# QUARTZ_01.net
KiCad netlist of a schematic drawn in EasyEDA Pro
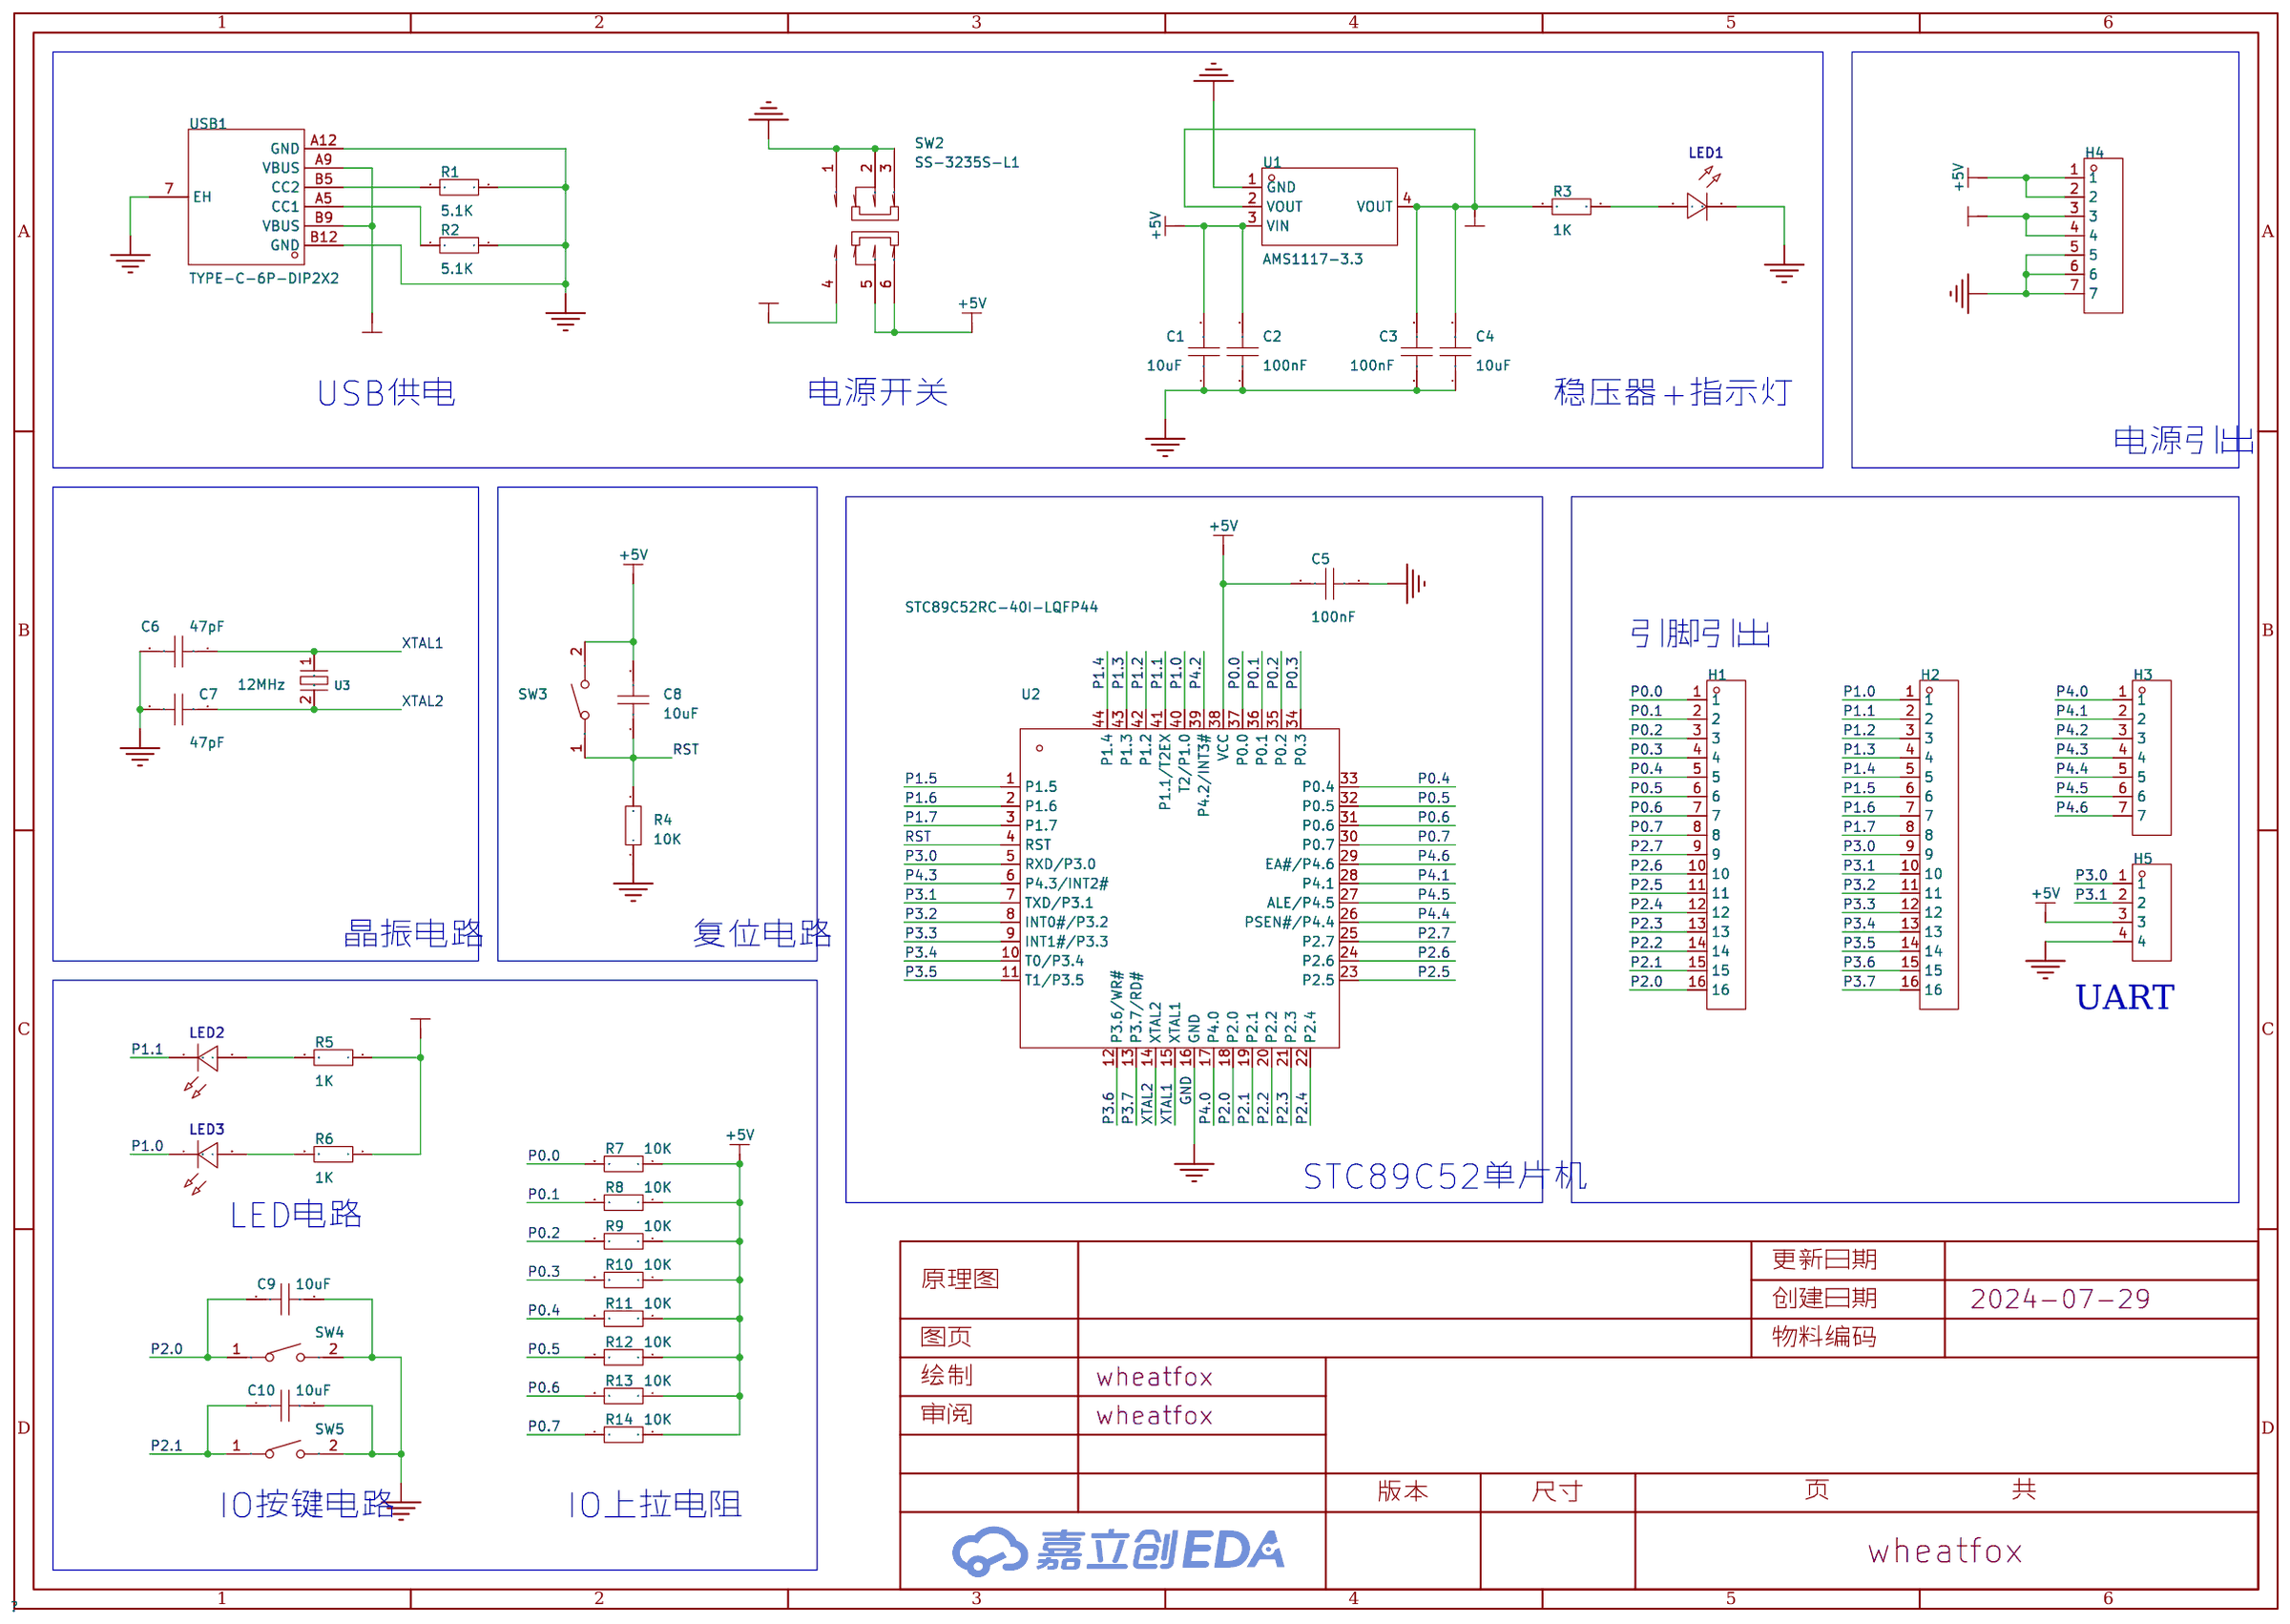
[diagram p0: schematic sheet]

(export (version "E")
  (design (tool "Eeschema 10.0.6"))
  (components
    (comp (ref "C1")
      (value "10uF")
      (footprint "easyedapro:C0805")
      (libsource (lib "easyedapro") (part "CapAcitance"))
    )
    (comp (ref "C2")
      (value "100nF")
      (footprint "easyedapro:C0805")
      (libsource (lib "easyedapro") (part "CapAcitance"))
    )
    (comp (ref "C3")
      (value "100nF")
      (footprint "easyedapro:C0805")
      (libsource (lib "easyedapro") (part "CapAcitance"))
    )
    (comp (ref "C4")
      (value "10uF")
      (footprint "easyedapro:C0805")
      (libsource (lib "easyedapro") (part "CapAcitance"))
    )
    (comp (ref "C5")
      (value "100nF")
      (footprint "easyedapro:C0805")
      (libsource (lib "easyedapro") (part "CapAcitance"))
    )
    (comp (ref "C6")
      (value "47pF")
      (footprint "easyedapro:C0805")
      (libsource (lib "easyedapro") (part "CapAcitance"))
    )
    (comp (ref "C7")
      (value "47pF")
      (footprint "easyedapro:C0805")
      (libsource (lib "easyedapro") (part "CapAcitance"))
    )
    (comp (ref "C8")
      (value "10uF")
      (footprint "easyedapro:C0805")
      (libsource (lib "easyedapro") (part "CapAcitance"))
    )
    (comp (ref "C9")
      (value "10uF")
      (footprint "easyedapro:C0805")
      (libsource (lib "easyedapro") (part "CapAcitance"))
    )
    (comp (ref "C10")
      (value "10uF")
      (footprint "easyedapro:C0805")
      (libsource (lib "easyedapro") (part "CapAcitance"))
    )
    (comp (ref "H1")
      (value "~")
      (footprint "easyedapro:HDR-TH_16P-P2.54-V-M")
      (libsource (lib "easyedapro") (part "HDR_2.54-1x16P"))
    )
    (comp (ref "H2")
      (value "~")
      (footprint "easyedapro:HDR-TH_16P-P2.54-V-M")
      (libsource (lib "easyedapro") (part "HDR_2.54-1x16P"))
    )
    (comp (ref "H3")
      (value "~")
      (footprint "easyedapro:HDR-TH_7P-P2.54-V-M")
      (fields (field (name "Manufacturer Part") "PZ254V-11-07P") (field (name "Manufacturer") "XFCN(兴飞)"))
      (libsource (lib "easyedapro") (part "PZ254V-11-07P"))
    )
    (comp (ref "H4")
      (value "~")
      (footprint "easyedapro:HDR-TH_7P-P2.54-V-M")
      (fields (field (name "Manufacturer Part") "PZ254V-11-07P") (field (name "Manufacturer") "XFCN(兴飞)"))
      (libsource (lib "easyedapro") (part "PZ254V-11-07P"))
    )
    (comp (ref "H5")
      (value "~")
      (footprint "easyedapro:HDR-TH_4P-P2.54-V-M")
      (libsource (lib "easyedapro") (part "PZ254V-11-04P"))
    )
    (comp (ref "LED1")
      (value "~")
      (footprint "easyedapro:LED_0805")
      (libsource (lib "easyedapro") (part "LED_G"))
    )
    (comp (ref "LED2")
      (value "~")
      (footprint "easyedapro:LED_0805")
      (libsource (lib "easyedapro") (part "LED_G"))
    )
    (comp (ref "LED3")
      (value "~")
      (footprint "easyedapro:LED_0805")
      (libsource (lib "easyedapro") (part "LED_G"))
    )
    (comp (ref "R1") (value "5.1K") (footprint "easyedapro:R0805") (libsource (lib "easyedapro") (part "电阻")))
    (comp (ref "R2") (value "5.1K") (footprint "easyedapro:R0805") (libsource (lib "easyedapro") (part "电阻")))
    (comp (ref "R3") (value "1K") (footprint "easyedapro:R0805") (libsource (lib "easyedapro") (part "电阻")))
    (comp (ref "R4") (value "10K") (footprint "easyedapro:R0805") (libsource (lib "easyedapro") (part "电阻")))
    (comp (ref "R5") (value "1K") (footprint "easyedapro:R0805") (libsource (lib "easyedapro") (part "电阻")))
    (comp (ref "R6") (value "1K") (footprint "easyedapro:R0805") (libsource (lib "easyedapro") (part "电阻")))
    (comp (ref "R7") (value "10K") (footprint "easyedapro:R0805") (libsource (lib "easyedapro") (part "电阻")))
    (comp (ref "R8") (value "10K") (footprint "easyedapro:R0805") (libsource (lib "easyedapro") (part "电阻")))
    (comp (ref "R9") (value "10K") (footprint "easyedapro:R0805") (libsource (lib "easyedapro") (part "电阻")))
    (comp (ref "R10") (value "10K") (footprint "easyedapro:R0805") (libsource (lib "easyedapro") (part "电阻")))
    (comp (ref "R11") (value "10K") (footprint "easyedapro:R0805") (libsource (lib "easyedapro") (part "电阻")))
    (comp (ref "R12") (value "10K") (footprint "easyedapro:R0805") (libsource (lib "easyedapro") (part "电阻")))
    (comp (ref "R13") (value "10K") (footprint "easyedapro:R0805") (libsource (lib "easyedapro") (part "电阻")))
    (comp (ref "R14") (value "10K") (footprint "easyedapro:R0805") (libsource (lib "easyedapro") (part "电阻")))
    (comp (ref "SW2")
      (value "SS-3235S-L1")
      (footprint "easyedapro:SW-SMD_SS-3235S-LX")
      (description "电路结构:双刀双掷;安装方式:卧贴;开关颜色:黑色;额定电流(DC):50mA;额定电压(DC):12V;额定电流(AC):50mA;额定电压(AC):12V;机械寿命:1万次;")
      (fields (field (name "Manufacturer") "XKB Connectivity(中国星坤)"))
      (libsource (lib "easyedapro") (part "SS-3235S-L1"))
    )
    (comp (ref "SW3")
      (value "轻触按键3*4*H")
      (footprint "easyedapro:SW-SMD_L4.0-W2.9-LS5.0")
      (libsource (lib "easyedapro") (part "轻触按键3*4*H"))
    )
    (comp (ref "SW4")
      (value "轻触按键3*4*H")
      (footprint "easyedapro:SW-SMD_L4.0-W2.9-LS5.0")
      (libsource (lib "easyedapro") (part "轻触按键3*4*H"))
    )
    (comp (ref "SW5")
      (value "轻触按键3*4*H")
      (footprint "easyedapro:SW-SMD_L4.0-W2.9-LS5.0")
      (libsource (lib "easyedapro") (part "轻触按键3*4*H"))
    )
    (comp (ref "U1")
      (value "AMS1117-3.3")
      (footprint "easyedapro:SOT-223-3_L6.5-W3.4-P2.30-LS7.0-BR")
      (description "输出类型:固定;最大输入电压:-;输出电压:3.3V;最大输出电流:1A;电源纹波抑制比(PSRR):72dB@(120Hz);输出极性:正极;")
      (fields (field (name "Manufacturer") "AMS"))
      (libsource (lib "easyedapro") (part "AMS1117-3.3"))
    )
    (comp (ref "U2")
      (value "STC89C52RC-40I-LQFP44")
      (footprint "easyedapro:LQFP-44_L10.0-W10.0-P0.80-LS12.0-BL")
      (description "CPU内核:51系列;程序存储容量:8KB;RAM总容量:512Byte;GPIO端口数量:39;工作电压范围:3.3V~5.5V;CPU最大主频:-;程序存储器类型:FLASH;")
      (fields (field (name "Manufacturer") "STC(宏晶)"))
      (libsource (lib "easyedapro") (part "STC89C52RC-40I_C8707"))
    )
    (comp (ref "U3")
      (value "12MHz")
      (footprint "easyedapro:CRYSTAL-SMD_L11.4-W4.7-LS12.7")
      (description "频率:12MHz;常温频差:±30ppm;外接负载电容:18pF;频率稳定度(全温):±35ppm;")
      (fields
        (field (name "Manufacturer Part") "ABLS-12.000MHZ-B4H-T")
        (field (name "Manufacturer") "ABRACON")
      )
      (libsource (lib "easyedapro") (part "ABLS-12.000MHZ-B4H-T"))
    )
    (comp (ref "USB1")
      (value "TYPE-C-6P-DIP2X2")
      (footprint "easyedapro:TYPE-C-SMD_TYPE-C-6P")
      (libsource (lib "easyedapro") (part "TYPE-C-6P-DIP2X2"))
    )
  )
  (nets
    (net (code "1") (name "+5V") (class "Default")
      (node (ref "C1") (pin "2") (pinfunction "2_2") (pintype "input"))
      (node (ref "C2") (pin "2") (pinfunction "2_2") (pintype "input"))
      (node (ref "C5") (pin "2") (pinfunction "2_2") (pintype "input"))
      (node (ref "C8") (pin "1") (pinfunction "1_1") (pintype "input"))
      (node (ref "H4") (pin "1") (pinfunction "1_1") (pintype "unspecified"))
      (node (ref "H4") (pin "2") (pinfunction "2_2") (pintype "unspecified"))
      (node (ref "H5") (pin "3") (pinfunction "3_3") (pintype "unspecified"))
      (node (ref "R10") (pin "1") (pinfunction "1_1") (pintype "input"))
      (node (ref "R11") (pin "1") (pinfunction "1_1") (pintype "input"))
      (node (ref "R12") (pin "1") (pinfunction "1_1") (pintype "input"))
      (node (ref "R13") (pin "1") (pinfunction "1_1") (pintype "input"))
      (node (ref "R14") (pin "1") (pinfunction "1_1") (pintype "input"))
      (node (ref "R7") (pin "1") (pinfunction "1_1") (pintype "input"))
      (node (ref "R8") (pin "1") (pinfunction "1_1") (pintype "input"))
      (node (ref "R9") (pin "1") (pinfunction "1_1") (pintype "input"))
      (node (ref "SW2") (pin "5") (pinfunction "5_5") (pintype "unspecified"))
      (node (ref "SW2") (pin "6") (pinfunction "6_6") (pintype "unspecified"))
      (node (ref "SW3") (pin "2") (pinfunction "2_2") (pintype "unspecified"))
      (node (ref "U1") (pin "3") (pinfunction "VIN_3") (pintype "unspecified"))
      (node (ref "U2") (pin "38") (pinfunction "VCC_38") (pintype "unspecified"))
    )
    (net (code "2") (name "/P0.0") (class "Default")
      (node (ref "H1") (pin "1") (pinfunction "1_1") (pintype "input"))
      (node (ref "R7") (pin "2") (pinfunction "2_2") (pintype "input"))
      (node (ref "U2") (pin "37") (pinfunction "P0.0_37") (pintype "unspecified"))
    )
    (net (code "3") (name "/P0.1") (class "Default")
      (node (ref "H1") (pin "2") (pinfunction "2_2") (pintype "input"))
      (node (ref "R8") (pin "2") (pinfunction "2_2") (pintype "input"))
      (node (ref "U2") (pin "36") (pinfunction "P0.1_36") (pintype "unspecified"))
    )
    (net (code "4") (name "/P0.2") (class "Default")
      (node (ref "H1") (pin "3") (pinfunction "3_3") (pintype "input"))
      (node (ref "R9") (pin "2") (pinfunction "2_2") (pintype "input"))
      (node (ref "U2") (pin "35") (pinfunction "P0.2_35") (pintype "unspecified"))
    )
    (net (code "5") (name "/P0.3") (class "Default")
      (node (ref "H1") (pin "4") (pinfunction "4_4") (pintype "input"))
      (node (ref "R10") (pin "2") (pinfunction "2_2") (pintype "input"))
      (node (ref "U2") (pin "34") (pinfunction "P0.3_34") (pintype "unspecified"))
    )
    (net (code "6") (name "/P0.4") (class "Default")
      (node (ref "H1") (pin "5") (pinfunction "5_5") (pintype "input"))
      (node (ref "R11") (pin "2") (pinfunction "2_2") (pintype "input"))
      (node (ref "U2") (pin "33") (pinfunction "P0.4_33") (pintype "unspecified"))
    )
    (net (code "7") (name "/P0.5") (class "Default")
      (node (ref "H1") (pin "6") (pinfunction "6_6") (pintype "input"))
      (node (ref "R12") (pin "2") (pinfunction "2_2") (pintype "input"))
      (node (ref "U2") (pin "32") (pinfunction "P0.5_32") (pintype "unspecified"))
    )
    (net (code "8") (name "/P0.6") (class "Default")
      (node (ref "H1") (pin "7") (pinfunction "7_7") (pintype "input"))
      (node (ref "R13") (pin "2") (pinfunction "2_2") (pintype "input"))
      (node (ref "U2") (pin "31") (pinfunction "P0.6_31") (pintype "unspecified"))
    )
    (net (code "9") (name "/P0.7") (class "Default")
      (node (ref "H1") (pin "8") (pinfunction "8_8") (pintype "input"))
      (node (ref "R14") (pin "2") (pinfunction "2_2") (pintype "input"))
      (node (ref "U2") (pin "30") (pinfunction "P0.7_30") (pintype "unspecified"))
    )
    (net (code "10") (name "/P1.0") (class "Default")
      (node (ref "H2") (pin "1") (pinfunction "1_1") (pintype "input"))
      (node (ref "LED3") (pin "1") (pinfunction "C_1") (pintype "input"))
      (node (ref "U2") (pin "40") (pinfunction "T2/P1.0_40") (pintype "unspecified"))
    )
    (net (code "11") (name "/P1.1") (class "Default")
      (node (ref "H2") (pin "2") (pinfunction "2_2") (pintype "input"))
      (node (ref "LED2") (pin "1") (pinfunction "C_1") (pintype "input"))
      (node (ref "U2") (pin "41") (pinfunction "P1.1/T2EX_41") (pintype "unspecified"))
    )
    (net (code "12") (name "/P1.2") (class "Default")
      (node (ref "H2") (pin "3") (pinfunction "3_3") (pintype "input"))
      (node (ref "U2") (pin "42") (pinfunction "P1.2_42") (pintype "unspecified"))
    )
    (net (code "13") (name "/P1.3") (class "Default")
      (node (ref "H2") (pin "4") (pinfunction "4_4") (pintype "input"))
      (node (ref "U2") (pin "43") (pinfunction "P1.3_43") (pintype "unspecified"))
    )
    (net (code "14") (name "/P1.4") (class "Default")
      (node (ref "H2") (pin "5") (pinfunction "5_5") (pintype "input"))
      (node (ref "U2") (pin "44") (pinfunction "P1.4_44") (pintype "unspecified"))
    )
    (net (code "15") (name "/P1.5") (class "Default")
      (node (ref "H2") (pin "6") (pinfunction "6_6") (pintype "input"))
      (node (ref "U2") (pin "1") (pinfunction "P1.5_1") (pintype "unspecified"))
    )
    (net (code "16") (name "/P1.6") (class "Default")
      (node (ref "H2") (pin "7") (pinfunction "7_7") (pintype "input"))
      (node (ref "U2") (pin "2") (pinfunction "P1.6_2") (pintype "unspecified"))
    )
    (net (code "17") (name "/P1.7") (class "Default")
      (node (ref "H2") (pin "8") (pinfunction "8_8") (pintype "input"))
      (node (ref "U2") (pin "3") (pinfunction "P1.7_3") (pintype "unspecified"))
    )
    (net (code "18") (name "/P2.0") (class "Default")
      (node (ref "C9") (pin "1") (pinfunction "1_1") (pintype "input"))
      (node (ref "H1") (pin "16") (pinfunction "16_16") (pintype "input"))
      (node (ref "SW4") (pin "1") (pinfunction "1_1") (pintype "unspecified"))
      (node (ref "U2") (pin "18") (pinfunction "P2.0_18") (pintype "unspecified"))
    )
    (net (code "19") (name "/P2.1") (class "Default")
      (node (ref "C10") (pin "1") (pinfunction "1_1") (pintype "input"))
      (node (ref "H1") (pin "15") (pinfunction "15_15") (pintype "input"))
      (node (ref "SW5") (pin "1") (pinfunction "1_1") (pintype "unspecified"))
      (node (ref "U2") (pin "19") (pinfunction "P2.1_19") (pintype "unspecified"))
    )
    (net (code "20") (name "/P2.2") (class "Default")
      (node (ref "H1") (pin "14") (pinfunction "14_14") (pintype "input"))
      (node (ref "U2") (pin "20") (pinfunction "P2.2_20") (pintype "unspecified"))
    )
    (net (code "21") (name "/P2.3") (class "Default")
      (node (ref "H1") (pin "13") (pinfunction "13_13") (pintype "input"))
      (node (ref "U2") (pin "21") (pinfunction "P2.3_21") (pintype "unspecified"))
    )
    (net (code "22") (name "/P2.4") (class "Default")
      (node (ref "H1") (pin "12") (pinfunction "12_12") (pintype "input"))
      (node (ref "U2") (pin "22") (pinfunction "P2.4_22") (pintype "unspecified"))
    )
    (net (code "23") (name "/P2.5") (class "Default")
      (node (ref "H1") (pin "11") (pinfunction "11_11") (pintype "input"))
      (node (ref "U2") (pin "23") (pinfunction "P2.5_23") (pintype "unspecified"))
    )
    (net (code "24") (name "/P2.6") (class "Default")
      (node (ref "H1") (pin "10") (pinfunction "10_10") (pintype "input"))
      (node (ref "U2") (pin "24") (pinfunction "P2.6_24") (pintype "unspecified"))
    )
    (net (code "25") (name "/P2.7") (class "Default")
      (node (ref "H1") (pin "9") (pinfunction "9_9") (pintype "input"))
      (node (ref "U2") (pin "25") (pinfunction "P2.7_25") (pintype "unspecified"))
    )
    (net (code "26") (name "/P3.0") (class "Default")
      (node (ref "H2") (pin "9") (pinfunction "9_9") (pintype "input"))
      (node (ref "H5") (pin "1") (pinfunction "1_1") (pintype "unspecified"))
      (node (ref "U2") (pin "5") (pinfunction "RXD/P3.0_5") (pintype "unspecified"))
    )
    (net (code "27") (name "/P3.1") (class "Default")
      (node (ref "H2") (pin "10") (pinfunction "10_10") (pintype "input"))
      (node (ref "H5") (pin "2") (pinfunction "2_2") (pintype "unspecified"))
      (node (ref "U2") (pin "7") (pinfunction "TXD/P3.1_7") (pintype "unspecified"))
    )
    (net (code "28") (name "/P3.2") (class "Default")
      (node (ref "H2") (pin "11") (pinfunction "11_11") (pintype "input"))
      (node (ref "U2") (pin "8") (pinfunction "INT0#/P3.2_8") (pintype "unspecified"))
    )
    (net (code "29") (name "/P3.3") (class "Default")
      (node (ref "H2") (pin "12") (pinfunction "12_12") (pintype "input"))
      (node (ref "U2") (pin "9") (pinfunction "INT1#/P3.3_9") (pintype "unspecified"))
    )
    (net (code "30") (name "/P3.4") (class "Default")
      (node (ref "H2") (pin "13") (pinfunction "13_13") (pintype "input"))
      (node (ref "U2") (pin "10") (pinfunction "T0/P3.4_10") (pintype "unspecified"))
    )
    (net (code "31") (name "/P3.5") (class "Default")
      (node (ref "H2") (pin "14") (pinfunction "14_14") (pintype "input"))
      (node (ref "U2") (pin "11") (pinfunction "T1/P3.5_11") (pintype "unspecified"))
    )
    (net (code "32") (name "/P3.6") (class "Default")
      (node (ref "H2") (pin "15") (pinfunction "15_15") (pintype "input"))
      (node (ref "U2") (pin "12") (pinfunction "P3.6/WR#_12") (pintype "unspecified"))
    )
    (net (code "33") (name "/P3.7") (class "Default")
      (node (ref "H2") (pin "16") (pinfunction "16_16") (pintype "input"))
      (node (ref "U2") (pin "13") (pinfunction "P3.7/RD#_13") (pintype "unspecified"))
    )
    (net (code "34") (name "/P4.0") (class "Default")
      (node (ref "H3") (pin "1") (pinfunction "1_1") (pintype "unspecified"))
      (node (ref "U2") (pin "17") (pinfunction "P4.0_17") (pintype "unspecified"))
    )
    (net (code "35") (name "/P4.1") (class "Default")
      (node (ref "H3") (pin "2") (pinfunction "2_2") (pintype "unspecified"))
      (node (ref "U2") (pin "28") (pinfunction "P4.1_28") (pintype "unspecified"))
    )
    (net (code "36") (name "/P4.2") (class "Default")
      (node (ref "H3") (pin "3") (pinfunction "3_3") (pintype "unspecified"))
      (node (ref "U2") (pin "39") (pinfunction "P4.2/INT3#_39") (pintype "unspecified"))
    )
    (net (code "37") (name "/P4.3") (class "Default")
      (node (ref "H3") (pin "4") (pinfunction "4_4") (pintype "unspecified"))
      (node (ref "U2") (pin "6") (pinfunction "P4.3/INT2#_6") (pintype "unspecified"))
    )
    (net (code "38") (name "/P4.4") (class "Default")
      (node (ref "H3") (pin "5") (pinfunction "5_5") (pintype "unspecified"))
      (node (ref "U2") (pin "26") (pinfunction "PSEN#/P4.4_26") (pintype "unspecified"))
    )
    (net (code "39") (name "/P4.5") (class "Default")
      (node (ref "H3") (pin "6") (pinfunction "6_6") (pintype "unspecified"))
      (node (ref "U2") (pin "27") (pinfunction "ALE/P4.5_27") (pintype "unspecified"))
    )
    (net (code "40") (name "/P4.6") (class "Default")
      (node (ref "H3") (pin "7") (pinfunction "7_7") (pintype "unspecified"))
      (node (ref "U2") (pin "29") (pinfunction "EA#/P4.6_29") (pintype "unspecified"))
    )
    (net (code "41") (name "/RST") (class "Default")
      (node (ref "C8") (pin "2") (pinfunction "2_2") (pintype "input"))
      (node (ref "R4") (pin "2") (pinfunction "2_2") (pintype "input"))
      (node (ref "SW3") (pin "1") (pinfunction "1_1") (pintype "unspecified"))
      (node (ref "U2") (pin "4") (pinfunction "RST_4") (pintype "unspecified"))
    )
    (net (code "42") (name "/XTAL1") (class "Default")
      (node (ref "C6") (pin "1") (pinfunction "1_1") (pintype "input"))
      (node (ref "U2") (pin "15") (pinfunction "XTAL1_15") (pintype "unspecified"))
      (node (ref "U3") (pin "1") (pinfunction "1_1") (pintype "input"))
    )
    (net (code "43") (name "/XTAL2") (class "Default")
      (node (ref "C7") (pin "1") (pinfunction "1_1") (pintype "input"))
      (node (ref "U2") (pin "14") (pinfunction "XTAL2_14") (pintype "unspecified"))
      (node (ref "U3") (pin "2") (pinfunction "GND_2") (pintype "input"))
    )
    (net (code "44") (name "3.3V") (class "Default")
      (node (ref "C3") (pin "2") (pinfunction "2_2") (pintype "input"))
      (node (ref "C4") (pin "2") (pinfunction "2_2") (pintype "input"))
      (node (ref "H4") (pin "3") (pinfunction "3_3") (pintype "unspecified"))
      (node (ref "H4") (pin "4") (pinfunction "4_4") (pintype "unspecified"))
      (node (ref "R3") (pin "1") (pinfunction "1_1") (pintype "input"))
      (node (ref "R5") (pin "1") (pinfunction "1_1") (pintype "input"))
      (node (ref "R6") (pin "1") (pinfunction "1_1") (pintype "input"))
      (node (ref "U1") (pin "2") (pinfunction "VOUT_2") (pintype "unspecified"))
      (node (ref "U1") (pin "4") (pinfunction "VOUT_4") (pintype "unspecified"))
    )
    (net (code "45") (name "GND") (class "Default")
      (node (ref "C1") (pin "1") (pinfunction "1_1") (pintype "input"))
      (node (ref "C10") (pin "2") (pinfunction "2_2") (pintype "input"))
      (node (ref "C2") (pin "1") (pinfunction "1_1") (pintype "input"))
      (node (ref "C3") (pin "1") (pinfunction "1_1") (pintype "input"))
      (node (ref "C4") (pin "1") (pinfunction "1_1") (pintype "input"))
      (node (ref "C5") (pin "1") (pinfunction "1_1") (pintype "input"))
      (node (ref "C6") (pin "2") (pinfunction "2_2") (pintype "input"))
      (node (ref "C7") (pin "2") (pinfunction "2_2") (pintype "input"))
      (node (ref "C9") (pin "2") (pinfunction "2_2") (pintype "input"))
      (node (ref "H4") (pin "5") (pinfunction "5_5") (pintype "unspecified"))
      (node (ref "H4") (pin "6") (pinfunction "6_6") (pintype "unspecified"))
      (node (ref "H4") (pin "7") (pinfunction "7_7") (pintype "unspecified"))
      (node (ref "H5") (pin "4") (pinfunction "4_4") (pintype "unspecified"))
      (node (ref "LED1") (pin "1") (pinfunction "C_1") (pintype "input"))
      (node (ref "R1") (pin "2") (pinfunction "2_2") (pintype "input"))
      (node (ref "R2") (pin "2") (pinfunction "2_2") (pintype "input"))
      (node (ref "R4") (pin "1") (pinfunction "1_1") (pintype "input"))
      (node (ref "SW2") (pin "1") (pinfunction "1_1") (pintype "unspecified"))
      (node (ref "SW2") (pin "2") (pinfunction "2_2") (pintype "unspecified"))
      (node (ref "SW2") (pin "3") (pinfunction "3_3") (pintype "unspecified"))
      (node (ref "SW4") (pin "2") (pinfunction "2_2") (pintype "unspecified"))
      (node (ref "SW5") (pin "2") (pinfunction "2_2") (pintype "unspecified"))
      (node (ref "U1") (pin "1") (pinfunction "GND_1") (pintype "unspecified"))
      (node (ref "U2") (pin "16") (pinfunction "GND_16") (pintype "unspecified"))
      (node (ref "USB1") (pin "7") (pinfunction "EH_7") (pintype "unspecified"))
      (node (ref "USB1") (pin "A12") (pinfunction "GND_A12") (pintype "unspecified"))
      (node (ref "USB1") (pin "B12") (pinfunction "GND_B12") (pintype "unspecified"))
    )
    (net (code "46") (name "Net-(LED1-A)") (class "Default")
      (node (ref "LED1") (pin "2") (pinfunction "A_2") (pintype "input"))
      (node (ref "R3") (pin "2") (pinfunction "2_2") (pintype "input"))
    )
    (net (code "47") (name "Net-(LED2-A)") (class "Default")
      (node (ref "LED2") (pin "2") (pinfunction "A_2") (pintype "input"))
      (node (ref "R5") (pin "2") (pinfunction "2_2") (pintype "input"))
    )
    (net (code "48") (name "Net-(LED3-A)") (class "Default")
      (node (ref "LED3") (pin "2") (pinfunction "A_2") (pintype "input"))
      (node (ref "R6") (pin "2") (pinfunction "2_2") (pintype "input"))
    )
    (net (code "49") (name "Net-(USB1-CC1)") (class "Default")
      (node (ref "R2") (pin "1") (pinfunction "1_1") (pintype "input"))
      (node (ref "USB1") (pin "A5") (pinfunction "CC1_A5") (pintype "unspecified"))
    )
    (net (code "50") (name "Net-(USB1-CC2)") (class "Default")
      (node (ref "R1") (pin "1") (pinfunction "1_1") (pintype "input"))
      (node (ref "USB1") (pin "B5") (pinfunction "CC2_B5") (pintype "unspecified"))
    )
    (net (code "51") (name "VCC+5V") (class "Default")
      (node (ref "SW2") (pin "4") (pinfunction "4_4") (pintype "unspecified"))
      (node (ref "USB1") (pin "A9") (pinfunction "VBUS_A9") (pintype "unspecified"))
      (node (ref "USB1") (pin "B9") (pinfunction "VBUS_B9") (pintype "unspecified"))
    )
  )
)
